# tessel.net
KiCad netlist of a schematic drawn in EAGLE
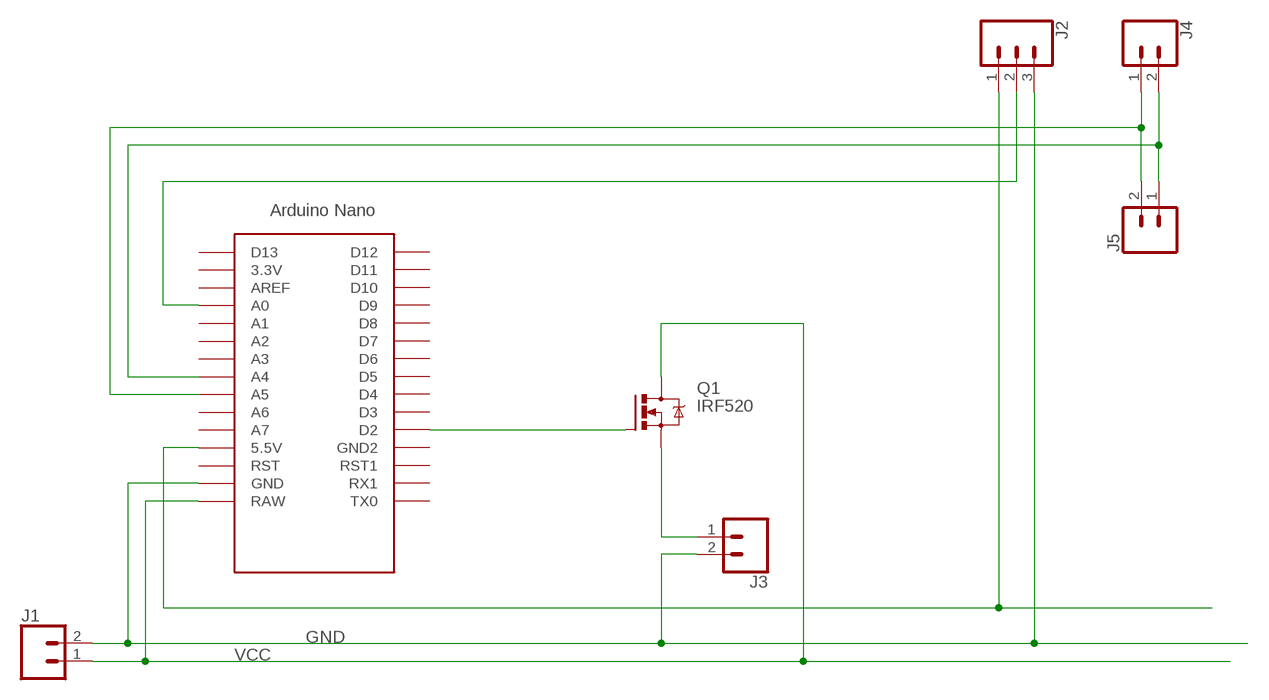
[diagram p0: schematic, sheet 1]

(export (version "E")
  (design (tool "Eeschema 10.0.6"))
  (components
    (comp (ref "J1")
      (value "CONN_023.5MM_LOCK")
      (footprint "eagle-import:SCREWTERMINAL-3.5MM-2_LOCK")
      (libsource (lib "eagle-import") (part "CONN_023.5MM_LOCK"))
    )
    (comp (ref "J2")
      (value "CONN_03LONGPADS")
      (footprint "eagle-import:1X03_LONGPADS")
      (libsource (lib "eagle-import") (part "CONN_03LONGPADS"))
    )
    (comp (ref "J3")
      (value "CONN_023.5MM_LOCK")
      (footprint "eagle-import:SCREWTERMINAL-3.5MM-2_LOCK")
      (libsource (lib "eagle-import") (part "CONN_023.5MM_LOCK"))
    )
    (comp (ref "J4")
      (value "CONN_023.5MM_LOCK")
      (footprint "eagle-import:SCREWTERMINAL-3.5MM-2_LOCK")
      (libsource (lib "eagle-import") (part "CONN_023.5MM_LOCK"))
    )
    (comp (ref "J5")
      (value "CONN_023.5MM_LOCK")
      (footprint "eagle-import:SCREWTERMINAL-3.5MM-2_LOCK")
      (libsource (lib "eagle-import") (part "CONN_023.5MM_LOCK"))
    )
    (comp (ref "Q1")
      (value "IRF520")
      (footprint "eagle-import:TO220BV")
      (libsource (lib "eagle-import") (part "IRF520"))
    )
    (comp (ref "U$1")
      (value "NANO")
      (footprint "eagle-import:NANO")
      (libsource (lib "eagle-import") (part "NANO"))
    )
  )
  (nets
    (net (code "1") (name "/GND") (class "Default")
      (node (ref "J1") (pin "2") (pinfunction "2_2") (pintype "passive"))
      (node (ref "J2") (pin "3") (pinfunction "3_3") (pintype "passive"))
      (node (ref "J3") (pin "2") (pinfunction "2_2") (pintype "passive"))
      (node (ref "U$1") (pin "GND") (pinfunction "GND_GND") (pintype "bidirectional"))
    )
    (net (code "2") (name "/VCC") (class "Default")
      (node (ref "J1") (pin "1") (pinfunction "1_1") (pintype "passive"))
      (node (ref "Q1") (pin "D") (pinfunction "D_D") (pintype "passive"))
      (node (ref "U$1") (pin "RAW") (pinfunction "RAW_RAW") (pintype "bidirectional"))
    )
    (net (code "3") (name "Net-(J2-Pad2)") (class "Default")
      (node (ref "J2") (pin "2") (pinfunction "2_2") (pintype "passive"))
      (node (ref "U$1") (pin "A0") (pinfunction "A0_A0") (pintype "bidirectional"))
    )
    (net (code "4") (name "Net-(J3-Pad1)") (class "Default")
      (node (ref "J3") (pin "1") (pinfunction "1_1") (pintype "passive"))
      (node (ref "Q1") (pin "S") (pinfunction "S_S") (pintype "passive"))
    )
    (net (code "5") (name "Net-(J4-Pad1)") (class "Default")
      (node (ref "J4") (pin "1") (pinfunction "1_1") (pintype "passive"))
      (node (ref "J5") (pin "2") (pinfunction "2_2") (pintype "passive"))
      (node (ref "U$1") (pin "A5") (pinfunction "A5_A5") (pintype "bidirectional"))
    )
    (net (code "6") (name "Net-(J4-Pad2)") (class "Default")
      (node (ref "J4") (pin "2") (pinfunction "2_2") (pintype "passive"))
      (node (ref "J5") (pin "1") (pinfunction "1_1") (pintype "passive"))
      (node (ref "U$1") (pin "A4") (pinfunction "A4_A4") (pintype "bidirectional"))
    )
    (net (code "7") (name "Net-(Q1-PadG)") (class "Default")
      (node (ref "Q1") (pin "G") (pinfunction "G_G") (pintype "passive"))
      (node (ref "U$1") (pin "D2") (pinfunction "D2_D2") (pintype "bidirectional"))
    )
    (net (code "8") (name "Net-(U$1-5.5V)") (class "Default")
      (node (ref "J2") (pin "1") (pinfunction "1_1") (pintype "passive"))
      (node (ref "U$1") (pin "5V") (pinfunction "5.5V_5V") (pintype "bidirectional"))
    )
    (net (code "9") (name "unconnected-(U$1-GND2-PadGND1)") (class "Default")
      (node (ref "U$1") (pin "GND1") (pinfunction "GND2_GND1") (pintype "bidirectional"))
    )
    (net (code "10") (name "unconnected-(U$1-Pad3.3V)") (class "Default")
      (node (ref "U$1") (pin "3.3V") (pinfunction "3.3V_3.3V") (pintype "bidirectional"))
    )
    (net (code "11") (name "unconnected-(U$1-PadA1)") (class "Default")
      (node (ref "U$1") (pin "A1") (pinfunction "A1_A1") (pintype "bidirectional"))
    )
    (net (code "12") (name "unconnected-(U$1-PadA2)") (class "Default")
      (node (ref "U$1") (pin "A2") (pinfunction "A2_A2") (pintype "bidirectional"))
    )
    (net (code "13") (name "unconnected-(U$1-PadA3)") (class "Default")
      (node (ref "U$1") (pin "A3") (pinfunction "A3_A3") (pintype "bidirectional"))
    )
    (net (code "14") (name "unconnected-(U$1-PadA6)") (class "Default")
      (node (ref "U$1") (pin "A6") (pinfunction "A6_A6") (pintype "bidirectional"))
    )
    (net (code "15") (name "unconnected-(U$1-PadA7)") (class "Default")
      (node (ref "U$1") (pin "A7") (pinfunction "A7_A7") (pintype "bidirectional"))
    )
    (net (code "16") (name "unconnected-(U$1-PadAREF)") (class "Default")
      (node (ref "U$1") (pin "AREF") (pinfunction "AREF_AREF") (pintype "bidirectional"))
    )
    (net (code "17") (name "unconnected-(U$1-PadD3)") (class "Default")
      (node (ref "U$1") (pin "D3") (pinfunction "D3_D3") (pintype "bidirectional"))
    )
    (net (code "18") (name "unconnected-(U$1-PadD4)") (class "Default")
      (node (ref "U$1") (pin "D4") (pinfunction "D4_D4") (pintype "bidirectional"))
    )
    (net (code "19") (name "unconnected-(U$1-PadD5)") (class "Default")
      (node (ref "U$1") (pin "D5") (pinfunction "D5_D5") (pintype "bidirectional"))
    )
    (net (code "20") (name "unconnected-(U$1-PadD6)") (class "Default")
      (node (ref "U$1") (pin "D6") (pinfunction "D6_D6") (pintype "bidirectional"))
    )
    (net (code "21") (name "unconnected-(U$1-PadD7)") (class "Default")
      (node (ref "U$1") (pin "D7") (pinfunction "D7_D7") (pintype "bidirectional"))
    )
    (net (code "22") (name "unconnected-(U$1-PadD8)") (class "Default")
      (node (ref "U$1") (pin "D8") (pinfunction "D8_D8") (pintype "bidirectional"))
    )
    (net (code "23") (name "unconnected-(U$1-PadD9)") (class "Default")
      (node (ref "U$1") (pin "D9") (pinfunction "D9_D9") (pintype "bidirectional"))
    )
    (net (code "24") (name "unconnected-(U$1-PadD10)") (class "Default")
      (node (ref "U$1") (pin "D10") (pinfunction "D10_D10") (pintype "bidirectional"))
    )
    (net (code "25") (name "unconnected-(U$1-PadD11)") (class "Default")
      (node (ref "U$1") (pin "D11") (pinfunction "D11_D11") (pintype "bidirectional"))
    )
    (net (code "26") (name "unconnected-(U$1-PadD12)") (class "Default")
      (node (ref "U$1") (pin "D12") (pinfunction "D12_D12") (pintype "bidirectional"))
    )
    (net (code "27") (name "unconnected-(U$1-PadD13)") (class "Default")
      (node (ref "U$1") (pin "D13") (pinfunction "D13_D13") (pintype "bidirectional"))
    )
    (net (code "28") (name "unconnected-(U$1-PadICSP1)") (class "Default")
      (node (ref "U$1") (pin "ICSP1") (pinfunction "ICSP1_ICSP1") (pintype "bidirectional"))
    )
    (net (code "29") (name "unconnected-(U$1-PadICSP2)") (class "Default")
      (node (ref "U$1") (pin "ICSP2") (pinfunction "ICSP2_ICSP2") (pintype "bidirectional"))
    )
    (net (code "30") (name "unconnected-(U$1-PadICSP3)") (class "Default")
      (node (ref "U$1") (pin "ICSP3") (pinfunction "ICSP3_ICSP3") (pintype "bidirectional"))
    )
    (net (code "31") (name "unconnected-(U$1-PadICSP4)") (class "Default")
      (node (ref "U$1") (pin "ICSP4") (pinfunction "ICSP4_ICSP4") (pintype "bidirectional"))
    )
    (net (code "32") (name "unconnected-(U$1-PadICSP5)") (class "Default")
      (node (ref "U$1") (pin "ICSP5") (pinfunction "ICSP5_ICSP5") (pintype "bidirectional"))
    )
    (net (code "33") (name "unconnected-(U$1-PadICSP6)") (class "Default")
      (node (ref "U$1") (pin "ICSP6") (pinfunction "ICSP6_ICSP6") (pintype "bidirectional"))
    )
    (net (code "34") (name "unconnected-(U$1-PadRST)") (class "Default")
      (node (ref "U$1") (pin "RST") (pinfunction "RST_RST") (pintype "bidirectional"))
    )
    (net (code "35") (name "unconnected-(U$1-PadRST1)") (class "Default")
      (node (ref "U$1") (pin "RST1") (pinfunction "RST1_RST1") (pintype "bidirectional"))
    )
    (net (code "36") (name "unconnected-(U$1-PadRX1)") (class "Default")
      (node (ref "U$1") (pin "RX1") (pinfunction "RX1_RX1") (pintype "bidirectional"))
    )
    (net (code "37") (name "unconnected-(U$1-PadTX0)") (class "Default")
      (node (ref "U$1") (pin "TX0") (pinfunction "TX0_TX0") (pintype "bidirectional"))
    )
  )
)
